# 611_jetbot_127.net
KiCad netlist of a schematic drawn in EAGLE
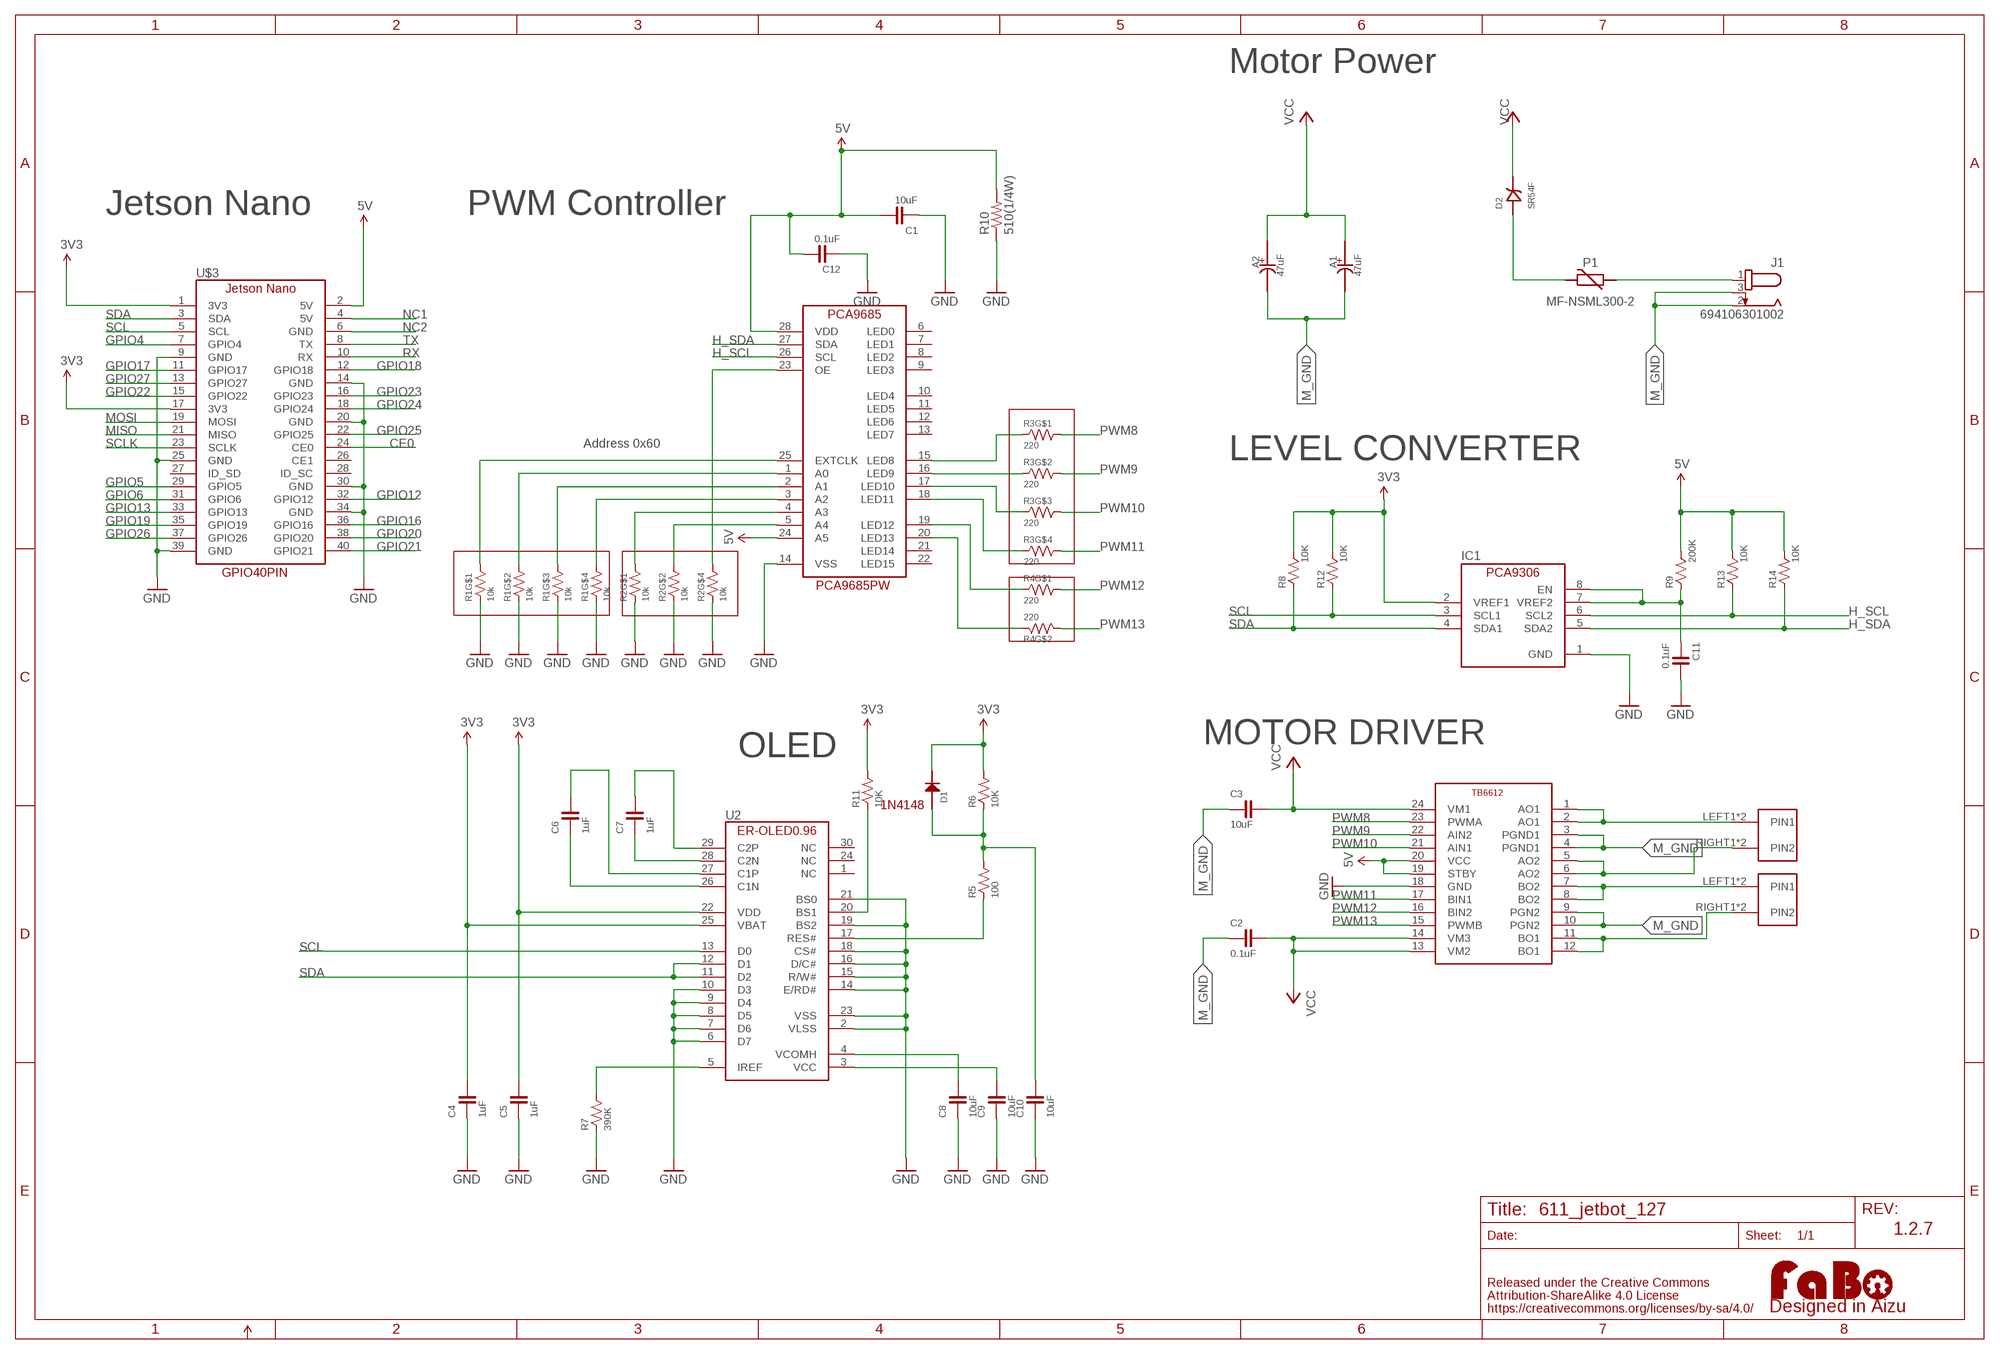
[diagram p0: schematic, sheet 1]

(export (version "E")
  (design (tool "Eeschema 10.0.6"))
  (components
    (comp (ref "A1")
      (value "47uF")
      (footprint "eagle-import:D60")
      (libsource (lib "eagle-import") (part "CAPACITOR-ALUMIN_D60"))
    )
    (comp (ref "A2")
      (value "47uF")
      (footprint "eagle-import:D60")
      (libsource (lib "eagle-import") (part "CAPACITOR-ALUMIN_D60"))
    )
    (comp (ref "C1")
      (value "10uF")
      (footprint "eagle-import:0603")
      (libsource (lib "eagle-import") (part "CAPACITOR-0603"))
    )
    (comp (ref "C2")
      (value "0.1uF")
      (footprint "eagle-import:0603")
      (libsource (lib "eagle-import") (part "CAPACITOR-0603"))
    )
    (comp (ref "C3")
      (value "10uF")
      (footprint "eagle-import:0603")
      (libsource (lib "eagle-import") (part "CAPACITOR-0603"))
    )
    (comp (ref "C4")
      (value "1uF")
      (footprint "eagle-import:0603-BOTTOM")
      (libsource (lib "eagle-import") (part "CAPACITOR-0603-BOTTOM"))
    )
    (comp (ref "C5")
      (value "1uF")
      (footprint "eagle-import:0603-BOTTOM")
      (libsource (lib "eagle-import") (part "CAPACITOR-0603-BOTTOM"))
    )
    (comp (ref "C6")
      (value "1uF")
      (footprint "eagle-import:0603-BOTTOM")
      (libsource (lib "eagle-import") (part "CAPACITOR-0603-BOTTOM"))
    )
    (comp (ref "C7")
      (value "1uF")
      (footprint "eagle-import:0603-BOTTOM")
      (libsource (lib "eagle-import") (part "CAPACITOR-0603-BOTTOM"))
    )
    (comp (ref "C8")
      (value "10uF")
      (footprint "eagle-import:0603-BOTTOM")
      (libsource (lib "eagle-import") (part "CAPACITOR-0603-BOTTOM"))
    )
    (comp (ref "C9")
      (value "10uF")
      (footprint "eagle-import:0603-BOTTOM")
      (libsource (lib "eagle-import") (part "CAPACITOR-0603-BOTTOM"))
    )
    (comp (ref "C10")
      (value "10uF")
      (footprint "eagle-import:0603-BOTTOM")
      (libsource (lib "eagle-import") (part "CAPACITOR-0603-BOTTOM"))
    )
    (comp (ref "C11")
      (value "0.1uF")
      (footprint "eagle-import:0603")
      (libsource (lib "eagle-import") (part "CAPACITOR-0603"))
    )
    (comp (ref "C12")
      (value "0.1uF")
      (footprint "eagle-import:0603")
      (libsource (lib "eagle-import") (part "CAPACITOR-0603"))
    )
    (comp (ref "D1")
      (value "1N4148")
      (footprint "eagle-import:1N4148W")
      (libsource (lib "eagle-import") (part "1N4148"))
    )
    (comp (ref "D2")
      (value "SR54F")
      (footprint "eagle-import:SMBF")
      (libsource (lib "eagle-import") (part "SR54F"))
    )
    (comp (ref "IC1")
      (value "PCA9306_SSOP")
      (footprint "eagle-import:8PIN-SSOP")
      (libsource (lib "eagle-import") (part "PCA9306_SSOP"))
    )
    (comp (ref "IC4")
      (value "PCA9685")
      (footprint "eagle-import:PCA9685")
      (libsource (lib "eagle-import") (part "PCA9685"))
    )
    (comp (ref "J1")
      (value "694106301002")
      (footprint "eagle-import:694106301002")
      (fields
        (field (name "DIGIKEY_PART_NUMBER") "732-5930-ND")
        (field (name "MANUFACTURER") "Wurth Electronics Inc.")
        (field (name "CREATED_BY") "PCBLayout.com")
      )
      (libsource (lib "eagle-import") (part "694106301002"))
    )
    (comp (ref "LOGO1")
      (value "LOGO_FABO-M")
      (footprint "eagle-import:LOGO_FABO_M")
      (libsource (lib "eagle-import") (part "LOGO_FABO-M"))
    )
    (comp (ref "P1")
      (value "MF-NSML300-2")
      (footprint "eagle-import:1206")
      (libsource (lib "eagle-import") (part "POLYSWITCH1206"))
    )
    (comp (ref "R1")
      (value "10k")
      (footprint "eagle-import:EXBV8V")
      (libsource (lib "eagle-import") (part "RESISTOR_ARRAY"))
    )
    (comp (ref "R2")
      (value "10k")
      (footprint "eagle-import:EXBV8V")
      (libsource (lib "eagle-import") (part "RESISTOR_ARRAY"))
    )
    (comp (ref "R3")
      (value "220")
      (footprint "eagle-import:EXBV8V")
      (libsource (lib "eagle-import") (part "RESISTOR_ARRAY"))
    )
    (comp (ref "R4")
      (value "220")
      (footprint "eagle-import:EXBV8V")
      (libsource (lib "eagle-import") (part "RESISTOR_ARRAY"))
    )
    (comp (ref "R5")
      (value "100")
      (footprint "eagle-import:0603-BOTTOM")
      (libsource (lib "eagle-import") (part "RESISTOR-0603-BOTTOM"))
    )
    (comp (ref "R6")
      (value "10K")
      (footprint "eagle-import:0603-BOTTOM")
      (libsource (lib "eagle-import") (part "RESISTOR-0603-BOTTOM"))
    )
    (comp (ref "R7")
      (value "390K")
      (footprint "eagle-import:0603-BOTTOM")
      (libsource (lib "eagle-import") (part "RESISTOR-0603-BOTTOM"))
    )
    (comp (ref "R8")
      (value "10K")
      (footprint "eagle-import:0603")
      (libsource (lib "eagle-import") (part "RESISTOR-0603"))
    )
    (comp (ref "R9")
      (value "200K")
      (footprint "eagle-import:0603")
      (libsource (lib "eagle-import") (part "RESISTOR-0603"))
    )
    (comp (ref "R10")
      (value "510(1/4W)")
      (footprint "eagle-import:R0805")
      (libsource (lib "eagle-import") (part "R-US_R0805"))
    )
    (comp (ref "R11")
      (value "10K")
      (footprint "eagle-import:0603-BOTTOM")
      (libsource (lib "eagle-import") (part "RESISTOR-0603-BOTTOM"))
    )
    (comp (ref "R12")
      (value "10K")
      (footprint "eagle-import:0603")
      (libsource (lib "eagle-import") (part "RESISTOR-0603"))
    )
    (comp (ref "R13")
      (value "10K")
      (footprint "eagle-import:0603")
      (libsource (lib "eagle-import") (part "RESISTOR-0603"))
    )
    (comp (ref "R14")
      (value "10K")
      (footprint "eagle-import:0603")
      (libsource (lib "eagle-import") (part "RESISTOR-0603"))
    )
    (comp (ref "U$3")
      (value "JETSON_NANO")
      (footprint "eagle-import:JETSON_NANO")
      (libsource (lib "eagle-import") (part "JETSON_NANO"))
    )
    (comp (ref "U$5")
      (value "TB6612")
      (footprint "eagle-import:TB6612")
      (libsource (lib "eagle-import") (part "TB6612"))
    )
    (comp (ref "U$6")
      (value "ML-1400-S1")
      (footprint "eagle-import:ML-1400-S1")
      (libsource (lib "eagle-import") (part "ML-1400-S1"))
    )
    (comp (ref "U$8")
      (value "ML-1400-S1")
      (footprint "eagle-import:ML-1400-S1")
      (libsource (lib "eagle-import") (part "ML-1400-S1"))
    )
    (comp (ref "U2")
      (value "ER-OLED0.96-1ER-CON30HT-1_REV2")
      (footprint "eagle-import:ER-CON30HT-1_REV2")
      (libsource (lib "eagle-import") (part "ER-OLED0.96-1ER-CON30HT-1_REV2"))
    )
  )
  (nets
    (net (code "1") (name "/CE0") (class "Default")
      (node (ref "U$3") (pin "24") (pinfunction "CE0_24") (pintype "bidirectional"))
    )
    (net (code "2") (name "/GPIO4") (class "Default")
      (node (ref "U$3") (pin "7") (pinfunction "GPIO4_7") (pintype "bidirectional"))
    )
    (net (code "3") (name "/GPIO5") (class "Default")
      (node (ref "U$3") (pin "29") (pinfunction "GPIO5_29") (pintype "bidirectional"))
    )
    (net (code "4") (name "/GPIO6") (class "Default")
      (node (ref "U$3") (pin "31") (pinfunction "GPIO6_31") (pintype "bidirectional"))
    )
    (net (code "5") (name "/GPIO12") (class "Default")
      (node (ref "U$3") (pin "32") (pinfunction "GPIO12_32") (pintype "bidirectional"))
    )
    (net (code "6") (name "/GPIO13") (class "Default")
      (node (ref "U$3") (pin "33") (pinfunction "GPIO13_33") (pintype "bidirectional"))
    )
    (net (code "7") (name "/GPIO16") (class "Default")
      (node (ref "U$3") (pin "36") (pinfunction "GPIO16_36") (pintype "bidirectional"))
    )
    (net (code "8") (name "/GPIO17") (class "Default")
      (node (ref "U$3") (pin "11") (pinfunction "GPIO17_11") (pintype "bidirectional"))
    )
    (net (code "9") (name "/GPIO18") (class "Default")
      (node (ref "U$3") (pin "12") (pinfunction "GPIO18_12") (pintype "bidirectional"))
    )
    (net (code "10") (name "/GPIO19") (class "Default")
      (node (ref "U$3") (pin "35") (pinfunction "GPIO19_35") (pintype "bidirectional"))
    )
    (net (code "11") (name "/GPIO20") (class "Default")
      (node (ref "U$3") (pin "38") (pinfunction "GPIO20_38") (pintype "bidirectional"))
    )
    (net (code "12") (name "/GPIO21") (class "Default")
      (node (ref "U$3") (pin "40") (pinfunction "GPIO21_40") (pintype "bidirectional"))
    )
    (net (code "13") (name "/GPIO22") (class "Default")
      (node (ref "U$3") (pin "15") (pinfunction "GPIO22_15") (pintype "bidirectional"))
    )
    (net (code "14") (name "/GPIO23") (class "Default")
      (node (ref "U$3") (pin "16") (pinfunction "GPIO23_16") (pintype "bidirectional"))
    )
    (net (code "15") (name "/GPIO24") (class "Default")
      (node (ref "U$3") (pin "18") (pinfunction "GPIO24_18") (pintype "bidirectional"))
    )
    (net (code "16") (name "/GPIO25") (class "Default")
      (node (ref "U$3") (pin "22") (pinfunction "GPIO25_22") (pintype "bidirectional"))
    )
    (net (code "17") (name "/GPIO26") (class "Default")
      (node (ref "U$3") (pin "37") (pinfunction "GPIO26_37") (pintype "bidirectional"))
    )
    (net (code "18") (name "/GPIO27") (class "Default")
      (node (ref "U$3") (pin "13") (pinfunction "GPIO27_13") (pintype "bidirectional"))
    )
    (net (code "19") (name "/H_SCL") (class "Default")
      (node (ref "IC1") (pin "6") (pinfunction "SCL2_6") (pintype "bidirectional"))
      (node (ref "IC4") (pin "26") (pinfunction "SCL_26") (pintype "bidirectional"))
      (node (ref "R13") (pin "1") (pinfunction "1_1") (pintype "bidirectional"))
    )
    (net (code "20") (name "/H_SDA") (class "Default")
      (node (ref "IC1") (pin "5") (pinfunction "SDA2_5") (pintype "bidirectional"))
      (node (ref "IC4") (pin "27") (pinfunction "SDA_27") (pintype "bidirectional"))
      (node (ref "R14") (pin "1") (pinfunction "1_1") (pintype "bidirectional"))
    )
    (net (code "21") (name "/MISO") (class "Default")
      (node (ref "U$3") (pin "21") (pinfunction "MISO_21") (pintype "bidirectional"))
    )
    (net (code "22") (name "/MOSI") (class "Default")
      (node (ref "U$3") (pin "19") (pinfunction "MOSI_19") (pintype "bidirectional"))
    )
    (net (code "23") (name "/NC1") (class "Default")
      (node (ref "U$3") (pin "4") (pinfunction "5V_4") (pintype "bidirectional"))
    )
    (net (code "24") (name "/NC2") (class "Default")
      (node (ref "U$3") (pin "6") (pinfunction "GND_6") (pintype "bidirectional"))
    )
    (net (code "25") (name "/PWM8") (class "Default")
      (node (ref "R3") (pin "8") (pinfunction "2_8") (pintype "bidirectional"))
      (node (ref "U$5") (pin "23") (pinfunction "PWMA_23") (pintype "bidirectional"))
    )
    (net (code "26") (name "/PWM9") (class "Default")
      (node (ref "R3") (pin "7") (pinfunction "2_7") (pintype "bidirectional"))
      (node (ref "U$5") (pin "22") (pinfunction "AIN2_22") (pintype "bidirectional"))
    )
    (net (code "27") (name "/PWM10") (class "Default")
      (node (ref "R3") (pin "6") (pinfunction "2_6") (pintype "bidirectional"))
      (node (ref "U$5") (pin "21") (pinfunction "AIN1_21") (pintype "bidirectional"))
    )
    (net (code "28") (name "/PWM11") (class "Default")
      (node (ref "R3") (pin "5") (pinfunction "2_5") (pintype "bidirectional"))
      (node (ref "U$5") (pin "17") (pinfunction "BIN1_17") (pintype "bidirectional"))
    )
    (net (code "29") (name "/PWM12") (class "Default")
      (node (ref "R4") (pin "8") (pinfunction "2_8") (pintype "bidirectional"))
      (node (ref "U$5") (pin "16") (pinfunction "BIN2_16") (pintype "bidirectional"))
    )
    (net (code "30") (name "/PWM13") (class "Default")
      (node (ref "R4") (pin "7") (pinfunction "2_7") (pintype "bidirectional"))
      (node (ref "U$5") (pin "15") (pinfunction "PWMB_15") (pintype "bidirectional"))
    )
    (net (code "31") (name "/RX") (class "Default")
      (node (ref "U$3") (pin "10") (pinfunction "RX_10") (pintype "bidirectional"))
    )
    (net (code "32") (name "/SCL") (class "Default")
      (node (ref "IC1") (pin "3") (pinfunction "SCL1_3") (pintype "bidirectional"))
      (node (ref "R12") (pin "1") (pinfunction "1_1") (pintype "bidirectional"))
      (node (ref "U$3") (pin "5") (pinfunction "SCL_5") (pintype "bidirectional"))
      (node (ref "U2") (pin "13") (pinfunction "D0_13") (pintype "bidirectional"))
    )
    (net (code "33") (name "/SCLK") (class "Default")
      (node (ref "U$3") (pin "23") (pinfunction "SCLK_23") (pintype "bidirectional"))
    )
    (net (code "34") (name "/SDA") (class "Default")
      (node (ref "IC1") (pin "4") (pinfunction "SDA1_4") (pintype "bidirectional"))
      (node (ref "R8") (pin "1") (pinfunction "1_1") (pintype "bidirectional"))
      (node (ref "U$3") (pin "3") (pinfunction "SDA_3") (pintype "bidirectional"))
      (node (ref "U2") (pin "11") (pinfunction "D2_11") (pintype "bidirectional"))
      (node (ref "U2") (pin "12") (pinfunction "D1_12") (pintype "bidirectional"))
    )
    (net (code "35") (name "/TX") (class "Default")
      (node (ref "U$3") (pin "8") (pinfunction "TX_8") (pintype "bidirectional"))
    )
    (net (code "36") (name "3V3") (class "Default")
      (node (ref "C4") (pin "2") (pinfunction "2_2") (pintype "passive"))
      (node (ref "C5") (pin "2") (pinfunction "2_2") (pintype "passive"))
      (node (ref "D1") (pin "CATHODE") (pinfunction "CATHODE_CATHODE") (pintype "bidirectional"))
      (node (ref "IC1") (pin "2") (pinfunction "VREF1_2") (pintype "bidirectional"))
      (node (ref "R11") (pin "2") (pinfunction "2_2") (pintype "bidirectional"))
      (node (ref "R12") (pin "2") (pinfunction "2_2") (pintype "bidirectional"))
      (node (ref "R6") (pin "2") (pinfunction "2_2") (pintype "bidirectional"))
      (node (ref "R8") (pin "2") (pinfunction "2_2") (pintype "bidirectional"))
      (node (ref "U$3") (pin "1") (pinfunction "3V3_1") (pintype "bidirectional"))
      (node (ref "U$3") (pin "17") (pinfunction "3V3_17") (pintype "bidirectional"))
      (node (ref "U2") (pin "22") (pinfunction "VDD_22") (pintype "bidirectional"))
      (node (ref "U2") (pin "25") (pinfunction "VBAT_25") (pintype "bidirectional"))
    )
    (net (code "37") (name "5V") (class "Default")
      (node (ref "C1") (pin "2") (pinfunction "2_2") (pintype "passive"))
      (node (ref "C12") (pin "2") (pinfunction "2_2") (pintype "passive"))
      (node (ref "IC4") (pin "24") (pinfunction "A5_24") (pintype "bidirectional"))
      (node (ref "IC4") (pin "28") (pinfunction "VDD_28") (pintype "bidirectional"))
      (node (ref "R10") (pin "2") (pinfunction "2_2") (pintype "passive"))
      (node (ref "R13") (pin "2") (pinfunction "2_2") (pintype "bidirectional"))
      (node (ref "R14") (pin "2") (pinfunction "2_2") (pintype "bidirectional"))
      (node (ref "R9") (pin "2") (pinfunction "2_2") (pintype "bidirectional"))
      (node (ref "U$3") (pin "2") (pinfunction "5V_2") (pintype "bidirectional"))
      (node (ref "U$5") (pin "19") (pinfunction "STBY_19") (pintype "bidirectional"))
      (node (ref "U$5") (pin "20") (pinfunction "VCC_20") (pintype "bidirectional"))
    )
    (net (code "38") (name "GND") (class "Default")
      (node (ref "C1") (pin "1") (pinfunction "1_1") (pintype "passive"))
      (node (ref "C10") (pin "1") (pinfunction "1_1") (pintype "passive"))
      (node (ref "C11") (pin "2") (pinfunction "2_2") (pintype "passive"))
      (node (ref "C12") (pin "1") (pinfunction "1_1") (pintype "passive"))
      (node (ref "C4") (pin "1") (pinfunction "1_1") (pintype "passive"))
      (node (ref "C5") (pin "1") (pinfunction "1_1") (pintype "passive"))
      (node (ref "C8") (pin "1") (pinfunction "1_1") (pintype "passive"))
      (node (ref "C9") (pin "1") (pinfunction "1_1") (pintype "passive"))
      (node (ref "IC1") (pin "1") (pinfunction "GND_1") (pintype "bidirectional"))
      (node (ref "IC4") (pin "14") (pinfunction "VSS_14") (pintype "bidirectional"))
      (node (ref "R1") (pin "1") (pinfunction "1_1") (pintype "bidirectional"))
      (node (ref "R1") (pin "2") (pinfunction "1_2") (pintype "bidirectional"))
      (node (ref "R1") (pin "3") (pinfunction "1_3") (pintype "bidirectional"))
      (node (ref "R1") (pin "4") (pinfunction "1_4") (pintype "bidirectional"))
      (node (ref "R10") (pin "1") (pinfunction "1_1") (pintype "passive"))
      (node (ref "R2") (pin "1") (pinfunction "1_1") (pintype "bidirectional"))
      (node (ref "R2") (pin "2") (pinfunction "1_2") (pintype "bidirectional"))
      (node (ref "R2") (pin "4") (pinfunction "1_4") (pintype "bidirectional"))
      (node (ref "R7") (pin "1") (pinfunction "1_1") (pintype "bidirectional"))
      (node (ref "U$3") (pin "14") (pinfunction "GND_14") (pintype "bidirectional"))
      (node (ref "U$3") (pin "20") (pinfunction "GND_20") (pintype "bidirectional"))
      (node (ref "U$3") (pin "25") (pinfunction "GND_25") (pintype "bidirectional"))
      (node (ref "U$3") (pin "30") (pinfunction "GND_30") (pintype "bidirectional"))
      (node (ref "U$3") (pin "34") (pinfunction "GND_34") (pintype "bidirectional"))
      (node (ref "U$3") (pin "39") (pinfunction "GND_39") (pintype "bidirectional"))
      (node (ref "U$3") (pin "9") (pinfunction "GND_9") (pintype "bidirectional"))
      (node (ref "U$5") (pin "18") (pinfunction "GND_18") (pintype "bidirectional"))
      (node (ref "U2") (pin "10") (pinfunction "D3_10") (pintype "bidirectional"))
      (node (ref "U2") (pin "14") (pinfunction "E/RD#_14") (pintype "bidirectional"))
      (node (ref "U2") (pin "15") (pinfunction "R/W#_15") (pintype "bidirectional"))
      (node (ref "U2") (pin "16") (pinfunction "D/C#_16") (pintype "bidirectional"))
      (node (ref "U2") (pin "18") (pinfunction "CS#_18") (pintype "bidirectional"))
      (node (ref "U2") (pin "19") (pinfunction "BS2_19") (pintype "bidirectional"))
      (node (ref "U2") (pin "2") (pinfunction "VLSS_2") (pintype "bidirectional"))
      (node (ref "U2") (pin "21") (pinfunction "BS0_21") (pintype "bidirectional"))
      (node (ref "U2") (pin "23") (pinfunction "VSS_23") (pintype "bidirectional"))
      (node (ref "U2") (pin "6") (pinfunction "D7_6") (pintype "bidirectional"))
      (node (ref "U2") (pin "7") (pinfunction "D6_7") (pintype "bidirectional"))
      (node (ref "U2") (pin "8") (pinfunction "D5_8") (pintype "bidirectional"))
      (node (ref "U2") (pin "9") (pinfunction "D4_9") (pintype "bidirectional"))
    )
    (net (code "39") (name "M_GND") (class "Default")
      (node (ref "A1") (pin "MINUS") (pinfunction "-_MINUS") (pintype "passive"))
      (node (ref "A2") (pin "MINUS") (pinfunction "-_MINUS") (pintype "passive"))
      (node (ref "C2") (pin "1") (pinfunction "1_1") (pintype "passive"))
      (node (ref "C3") (pin "1") (pinfunction "1_1") (pintype "passive"))
      (node (ref "J1") (pin "2") (pinfunction "2_2") (pintype "passive"))
      (node (ref "J1") (pin "3") (pinfunction "3_3") (pintype "passive"))
      (node (ref "U$5") (pin "10") (pinfunction "PGN2_10") (pintype "bidirectional"))
      (node (ref "U$5") (pin "3") (pinfunction "PGND1_3") (pintype "bidirectional"))
      (node (ref "U$5") (pin "4") (pinfunction "PGND1_4") (pintype "bidirectional"))
      (node (ref "U$5") (pin "9") (pinfunction "PGN2_9") (pintype "bidirectional"))
    )
    (net (code "40") (name "Net-(C10-Pad2)") (class "Default")
      (node (ref "C10") (pin "2") (pinfunction "2_2") (pintype "passive"))
      (node (ref "D1") (pin "ANODE") (pinfunction "ANODE_ANODE") (pintype "bidirectional"))
      (node (ref "R5") (pin "2") (pinfunction "2_2") (pintype "bidirectional"))
      (node (ref "R6") (pin "1") (pinfunction "1_1") (pintype "bidirectional"))
    )
    (net (code "41") (name "Net-(D2-PadANODE)") (class "Default")
      (node (ref "D2") (pin "ANODE") (pinfunction "ANODE_ANODE") (pintype "bidirectional"))
      (node (ref "P1") (pin "2") (pinfunction "2_2") (pintype "bidirectional"))
    )
    (net (code "42") (name "Net-(IC1-EN)") (class "Default")
      (node (ref "C11") (pin "1") (pinfunction "1_1") (pintype "passive"))
      (node (ref "IC1") (pin "7") (pinfunction "VREF2_7") (pintype "bidirectional"))
      (node (ref "IC1") (pin "8") (pinfunction "EN_8") (pintype "bidirectional"))
      (node (ref "R9") (pin "1") (pinfunction "1_1") (pintype "bidirectional"))
    )
    (net (code "43") (name "Net-(IC4-A0)") (class "Default")
      (node (ref "IC4") (pin "1") (pinfunction "A0_1") (pintype "bidirectional"))
      (node (ref "R1") (pin "7") (pinfunction "2_7") (pintype "bidirectional"))
    )
    (net (code "44") (name "Net-(IC4-A1)") (class "Default")
      (node (ref "IC4") (pin "2") (pinfunction "A1_2") (pintype "bidirectional"))
      (node (ref "R1") (pin "6") (pinfunction "2_6") (pintype "bidirectional"))
    )
    (net (code "45") (name "Net-(IC4-A2)") (class "Default")
      (node (ref "IC4") (pin "3") (pinfunction "A2_3") (pintype "bidirectional"))
      (node (ref "R1") (pin "5") (pinfunction "2_5") (pintype "bidirectional"))
    )
    (net (code "46") (name "Net-(IC4-A3)") (class "Default")
      (node (ref "IC4") (pin "4") (pinfunction "A3_4") (pintype "bidirectional"))
      (node (ref "R2") (pin "8") (pinfunction "2_8") (pintype "bidirectional"))
    )
    (net (code "47") (name "Net-(IC4-A4)") (class "Default")
      (node (ref "IC4") (pin "5") (pinfunction "A4_5") (pintype "bidirectional"))
      (node (ref "R2") (pin "7") (pinfunction "2_7") (pintype "bidirectional"))
    )
    (net (code "48") (name "Net-(IC4-EXTCLK)") (class "Default")
      (node (ref "IC4") (pin "25") (pinfunction "EXTCLK_25") (pintype "bidirectional"))
      (node (ref "R1") (pin "8") (pinfunction "2_8") (pintype "bidirectional"))
    )
    (net (code "49") (name "Net-(IC4-LED8)") (class "Default")
      (node (ref "IC4") (pin "15") (pinfunction "LED8_15") (pintype "bidirectional"))
      (node (ref "R3") (pin "1") (pinfunction "1_1") (pintype "bidirectional"))
    )
    (net (code "50") (name "Net-(IC4-LED9)") (class "Default")
      (node (ref "IC4") (pin "16") (pinfunction "LED9_16") (pintype "bidirectional"))
      (node (ref "R3") (pin "2") (pinfunction "1_2") (pintype "bidirectional"))
    )
    (net (code "51") (name "Net-(IC4-LED10)") (class "Default")
      (node (ref "IC4") (pin "17") (pinfunction "LED10_17") (pintype "bidirectional"))
      (node (ref "R3") (pin "3") (pinfunction "1_3") (pintype "bidirectional"))
    )
    (net (code "52") (name "Net-(IC4-LED11)") (class "Default")
      (node (ref "IC4") (pin "18") (pinfunction "LED11_18") (pintype "bidirectional"))
      (node (ref "R3") (pin "4") (pinfunction "1_4") (pintype "bidirectional"))
    )
    (net (code "53") (name "Net-(IC4-LED12)") (class "Default")
      (node (ref "IC4") (pin "19") (pinfunction "LED12_19") (pintype "bidirectional"))
      (node (ref "R4") (pin "1") (pinfunction "1_1") (pintype "bidirectional"))
    )
    (net (code "54") (name "Net-(IC4-LED13)") (class "Default")
      (node (ref "IC4") (pin "20") (pinfunction "LED13_20") (pintype "bidirectional"))
      (node (ref "R4") (pin "2") (pinfunction "1_2") (pintype "bidirectional"))
    )
    (net (code "55") (name "Net-(IC4-OE)") (class "Default")
      (node (ref "IC4") (pin "23") (pinfunction "OE_23") (pintype "bidirectional"))
      (node (ref "R2") (pin "5") (pinfunction "2_5") (pintype "bidirectional"))
    )
    (net (code "56") (name "Net-(J1-Pad1)") (class "Default")
      (node (ref "J1") (pin "1") (pinfunction "1_1") (pintype "passive"))
      (node (ref "P1") (pin "1") (pinfunction "1_1") (pintype "bidirectional"))
    )
    (net (code "57") (name "Net-(U$5-AO1-Pad1)") (class "Default")
      (node (ref "U$5") (pin "1") (pinfunction "AO1_1") (pintype "bidirectional"))
      (node (ref "U$5") (pin "2") (pinfunction "AO1_2") (pintype "bidirectional"))
      (node (ref "U$6") (pin "LEFT1") (pinfunction "PIN1_LEFT1") (pintype "bidirectional"))
      (node (ref "U$6") (pin "LEFT2") (pinfunction "PIN1_LEFT2") (pintype "bidirectional"))
    )
    (net (code "58") (name "Net-(U$5-AO2-Pad5)") (class "Default")
      (node (ref "U$5") (pin "5") (pinfunction "AO2_5") (pintype "bidirectional"))
      (node (ref "U$5") (pin "6") (pinfunction "AO2_6") (pintype "bidirectional"))
      (node (ref "U$6") (pin "RIGHT1") (pinfunction "PIN2_RIGHT1") (pintype "bidirectional"))
      (node (ref "U$6") (pin "RIGHT2") (pinfunction "PIN2_RIGHT2") (pintype "bidirectional"))
    )
    (net (code "59") (name "Net-(U$5-BO1-Pad11)") (class "Default")
      (node (ref "U$5") (pin "11") (pinfunction "BO1_11") (pintype "bidirectional"))
      (node (ref "U$5") (pin "12") (pinfunction "BO1_12") (pintype "bidirectional"))
      (node (ref "U$8") (pin "RIGHT1") (pinfunction "PIN2_RIGHT1") (pintype "bidirectional"))
      (node (ref "U$8") (pin "RIGHT2") (pinfunction "PIN2_RIGHT2") (pintype "bidirectional"))
    )
    (net (code "60") (name "Net-(U$5-BO2-Pad7)") (class "Default")
      (node (ref "U$5") (pin "7") (pinfunction "BO2_7") (pintype "bidirectional"))
      (node (ref "U$5") (pin "8") (pinfunction "BO2_8") (pintype "bidirectional"))
      (node (ref "U$8") (pin "LEFT1") (pinfunction "PIN1_LEFT1") (pintype "bidirectional"))
      (node (ref "U$8") (pin "LEFT2") (pinfunction "PIN1_LEFT2") (pintype "bidirectional"))
    )
    (net (code "61") (name "Net-(U2-BS1)") (class "Default")
      (node (ref "R11") (pin "1") (pinfunction "1_1") (pintype "bidirectional"))
      (node (ref "U2") (pin "20") (pinfunction "BS1_20") (pintype "bidirectional"))
    )
    (net (code "62") (name "Net-(U2-C1N)") (class "Default")
      (node (ref "C6") (pin "1") (pinfunction "1_1") (pintype "passive"))
      (node (ref "U2") (pin "26") (pinfunction "C1N_26") (pintype "bidirectional"))
    )
    (net (code "63") (name "Net-(U2-C1P)") (class "Default")
      (node (ref "C6") (pin "2") (pinfunction "2_2") (pintype "passive"))
      (node (ref "U2") (pin "27") (pinfunction "C1P_27") (pintype "bidirectional"))
    )
    (net (code "64") (name "Net-(U2-C2N)") (class "Default")
      (node (ref "C7") (pin "1") (pinfunction "1_1") (pintype "passive"))
      (node (ref "U2") (pin "28") (pinfunction "C2N_28") (pintype "bidirectional"))
    )
    (net (code "65") (name "Net-(U2-C2P)") (class "Default")
      (node (ref "C7") (pin "2") (pinfunction "2_2") (pintype "passive"))
      (node (ref "U2") (pin "29") (pinfunction "C2P_29") (pintype "bidirectional"))
    )
    (net (code "66") (name "Net-(U2-IREF)") (class "Default")
      (node (ref "R7") (pin "2") (pinfunction "2_2") (pintype "bidirectional"))
      (node (ref "U2") (pin "5") (pinfunction "IREF_5") (pintype "bidirectional"))
    )
    (net (code "67") (name "Net-(U2-RES#)") (class "Default")
      (node (ref "R5") (pin "1") (pinfunction "1_1") (pintype "bidirectional"))
      (node (ref "U2") (pin "17") (pinfunction "RES#_17") (pintype "bidirectional"))
    )
    (net (code "68") (name "Net-(U2-VCC)") (class "Default")
      (node (ref "C9") (pin "2") (pinfunction "2_2") (pintype "passive"))
      (node (ref "U2") (pin "3") (pinfunction "VCC_3") (pintype "bidirectional"))
    )
    (net (code "69") (name "Net-(U2-VCOMH)") (class "Default")
      (node (ref "C8") (pin "2") (pinfunction "2_2") (pintype "passive"))
      (node (ref "U2") (pin "4") (pinfunction "VCOMH_4") (pintype "bidirectional"))
    )
    (net (code "70") (name "VCC") (class "Default")
      (node (ref "A1") (pin "PLUS") (pinfunction "+_PLUS") (pintype "passive"))
      (node (ref "A2") (pin "PLUS") (pinfunction "+_PLUS") (pintype "passive"))
      (node (ref "C2") (pin "2") (pinfunction "2_2") (pintype "passive"))
      (node (ref "C3") (pin "2") (pinfunction "2_2") (pintype "passive"))
      (node (ref "D2") (pin "CATHODE") (pinfunction "CATHODE_CATHODE") (pintype "bidirectional"))
      (node (ref "U$5") (pin "13") (pinfunction "VM2_13") (pintype "bidirectional"))
      (node (ref "U$5") (pin "14") (pinfunction "VM3_14") (pintype "bidirectional"))
      (node (ref "U$5") (pin "24") (pinfunction "VM1_24") (pintype "bidirectional"))
    )
    (net (code "71") (name "unconnected-(IC4-LED0-Pad6)") (class "Default")
      (node (ref "IC4") (pin "6") (pinfunction "LED0_6") (pintype "bidirectional"))
    )
    (net (code "72") (name "unconnected-(IC4-LED1-Pad7)") (class "Default")
      (node (ref "IC4") (pin "7") (pinfunction "LED1_7") (pintype "bidirectional"))
    )
    (net (code "73") (name "unconnected-(IC4-LED2-Pad8)") (class "Default")
      (node (ref "IC4") (pin "8") (pinfunction "LED2_8") (pintype "bidirectional"))
    )
    (net (code "74") (name "unconnected-(IC4-LED3-Pad9)") (class "Default")
      (node (ref "IC4") (pin "9") (pinfunction "LED3_9") (pintype "bidirectional"))
    )
    (net (code "75") (name "unconnected-(IC4-LED4-Pad10)") (class "Default")
      (node (ref "IC4") (pin "10") (pinfunction "LED4_10") (pintype "bidirectional"))
    )
    (net (code "76") (name "unconnected-(IC4-LED5-Pad11)") (class "Default")
      (node (ref "IC4") (pin "11") (pinfunction "LED5_11") (pintype "bidirectional"))
    )
    (net (code "77") (name "unconnected-(IC4-LED6-Pad12)") (class "Default")
      (node (ref "IC4") (pin "12") (pinfunction "LED6_12") (pintype "bidirectional"))
    )
    (net (code "78") (name "unconnected-(IC4-LED7-Pad13)") (class "Default")
      (node (ref "IC4") (pin "13") (pinfunction "LED7_13") (pintype "bidirectional"))
    )
    (net (code "79") (name "unconnected-(IC4-LED14-Pad21)") (class "Default")
      (node (ref "IC4") (pin "21") (pinfunction "LED14_21") (pintype "bidirectional"))
    )
    (net (code "80") (name "unconnected-(IC4-LED15-Pad22)") (class "Default")
      (node (ref "IC4") (pin "22") (pinfunction "LED15_22") (pintype "bidirectional"))
    )
    (net (code "81") (name "unconnected-(U$3-CE1-Pad26)") (class "Default")
      (node (ref "U$3") (pin "26") (pinfunction "CE1_26") (pintype "bidirectional"))
    )
    (net (code "82") (name "unconnected-(U$3-ID_SC-Pad28)") (class "Default")
      (node (ref "U$3") (pin "28") (pinfunction "ID_SC_28") (pintype "bidirectional"))
    )
    (net (code "83") (name "unconnected-(U$3-ID_SD-Pad27)") (class "Default")
      (node (ref "U$3") (pin "27") (pinfunction "ID_SD_27") (pintype "bidirectional"))
    )
    (net (code "84") (name "unconnected-(U2-NC-Pad1)") (class "Default")
      (node (ref "U2") (pin "1") (pinfunction "NC_1") (pintype "bidirectional"))
    )
    (net (code "85") (name "unconnected-(U2-NC-Pad24)") (class "Default")
      (node (ref "U2") (pin "24") (pinfunction "NC_24") (pintype "bidirectional"))
    )
    (net (code "86") (name "unconnected-(U2-NC-Pad30)") (class "Default")
      (node (ref "U2") (pin "30") (pinfunction "NC_30") (pintype "bidirectional"))
    )
  )
)
